# Boost_voltage_module_sheet.net
KiCad netlist of a schematic drawn in Altium Designer
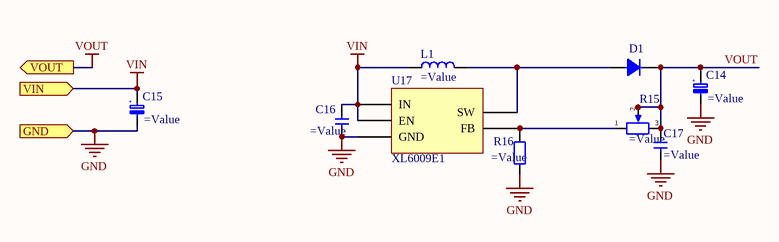
[diagram p0: Boost voltage module sheet.SchDoc]

(export (version "E")
  (design (tool "Eeschema 10.0.6"))
  (components
    (comp (ref "C14")
      (value "~")
      (footprint "D8C3.2H12")
      (libsource (lib "AlexChistiakov") (part "Cap Aluminum"))
    )
    (comp (ref "C15")
      (value "~")
      (footprint "D8C3.2H12")
      (libsource (lib "AlexChistiakov") (part "Cap Aluminum"))
    )
    (comp (ref "C16") (value "~") (footprint "cap0603") (libsource (lib "AlexChistiakov") (part "Cap SMD")))
    (comp (ref "C17") (value "~") (footprint "cap0603") (libsource (lib "AlexChistiakov") (part "Cap SMD")))
    (comp (ref "D1")
      (value "Diode SMD")
      (footprint "SOD123")
      (libsource (lib "AlexChistiakov") (part "Diode SMD"))
    )
    (comp (ref "L1") (value "~") (footprint "SRR1280") (libsource (lib "AlexChistiakov") (part "Inductor")))
    (comp (ref "R15")
      (value "~")
      (footprint "3224W")
      (libsource (lib "AlexChistiakov") (part "Potentiometer"))
    )
    (comp (ref "R16")
      (value "~")
      (footprint "res0603")
      (libsource (lib "AlexChistiakov") (part "Resistor SMD"))
    )
    (comp (ref "U17")
      (value "XL6009E1")
      (footprint "TO263-5L")
      (libsource (lib "AlexChistiakov") (part "XL6009E1"))
    )
  )
  (nets
    (net (code "1") (name "GND") (class "Default")
      (node (ref "C14") (pin "2") (pinfunction "MINUS_2") (pintype "passive"))
      (node (ref "C15") (pin "2") (pinfunction "MINUS_2") (pintype "passive"))
      (node (ref "C16") (pin "2") (pinfunction "2_2") (pintype "passive"))
      (node (ref "C17") (pin "2") (pinfunction "2_2") (pintype "passive"))
      (node (ref "R16") (pin "1") (pinfunction "1_1") (pintype "passive"))
      (node (ref "U17") (pin "1") (pinfunction "GND_1") (pintype "passive"))
    )
    (net (code "2") (name "Net-(U17-FB)") (class "Default")
      (node (ref "R15") (pin "1") (pinfunction "1_1") (pintype "passive"))
      (node (ref "R16") (pin "2") (pinfunction "2_2") (pintype "passive"))
      (node (ref "U17") (pin "5") (pinfunction "FB_5") (pintype "passive"))
    )
    (net (code "3") (name "Net-(U17-SW)") (class "Default")
      (node (ref "D1") (pin "1") (pinfunction "1_1") (pintype "passive"))
      (node (ref "L1") (pin "2") (pinfunction "2_2") (pintype "passive"))
      (node (ref "U17") (pin "3") (pinfunction "SW_3") (pintype "passive"))
    )
    (net (code "4") (name "VIN") (class "Default")
      (node (ref "C15") (pin "1") (pinfunction "PLUS_1") (pintype "passive"))
      (node (ref "C16") (pin "1") (pinfunction "1_1") (pintype "passive"))
      (node (ref "L1") (pin "1") (pinfunction "1_1") (pintype "passive"))
      (node (ref "U17") (pin "2") (pinfunction "EN_2") (pintype "passive"))
      (node (ref "U17") (pin "4") (pinfunction "IN_4") (pintype "passive"))
    )
    (net (code "5") (name "VOUT") (class "Default")
      (node (ref "C14") (pin "1") (pinfunction "PLUS_1") (pintype "passive"))
      (node (ref "C17") (pin "1") (pinfunction "1_1") (pintype "passive"))
      (node (ref "D1") (pin "2") (pinfunction "2_2") (pintype "passive"))
      (node (ref "R15") (pin "2") (pinfunction "2_2") (pintype "passive"))
      (node (ref "R15") (pin "3") (pinfunction "3_3") (pintype "passive"))
    )
  )
)
